# 5V.net
KiCad netlist of a schematic drawn in Altium Designer
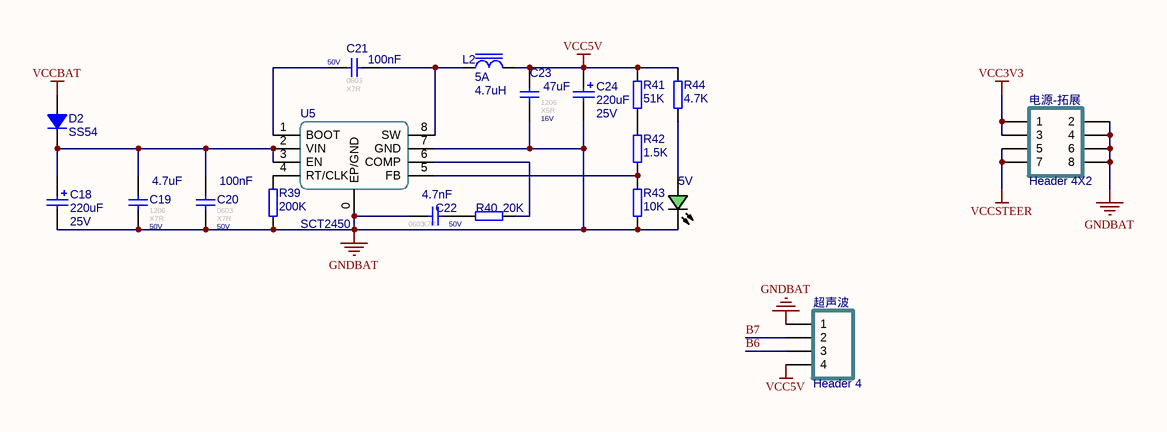
[diagram p0: 5V电源.SchDoc]

(export (version "E")
  (design (tool "Eeschema 10.0.6"))
  (components
    (comp (ref "5V")
      (value "翠绿贴片LED")
      (footprint "LEDC1608(0603)-L")
      (fields (field (name "PUBLISHER") "Altium Limited"))
      (libsource (lib "MM32F3277主板原理图库") (part "LED Chip Green"))
    )
    (comp (ref "C18")
      (value "220uF")
      (footprint "CAPS6.3")
      (description "Polarized Capacitor (Radial)")
      (fields
        (field (name "VOLTAGE") "25V")
        (field (name "Comment") "220uF 25V")
        (field (name "PUBLISHER") "Altium Limited")
      )
      (libsource (lib "MM32F3277主板原理图库") (part "Cap-Solid"))
    )
    (comp (ref "C19")
      (value "4.7uF")
      (footprint "1206")
      (description "贴片电容")
      (fields
        (field (name "TOLERANCE") "±10%")
        (field (name "TYPE") "X7R")
        (field (name "VOLTAGE") "50V")
        (field (name "Comment") "4.7uF ±10% 50V")
      )
      (libsource (lib "MM32F3277主板原理图库") (part "Cap-Chip_3"))
    )
    (comp (ref "C20")
      (value "100nF")
      (footprint "0603")
      (description "贴片电容")
      (fields
        (field (name "TOLERANCE") "±10%")
        (field (name "TYPE") "X7R")
        (field (name "VOLTAGE") "50V")
        (field (name "Comment") "100nF ±10% 50V")
      )
      (libsource (lib "MM32F3277主板原理图库") (part "Cap-Chip_2"))
    )
    (comp (ref "C21")
      (value "100nF")
      (footprint "0603")
      (description "贴片电容")
      (fields
        (field (name "TOLERANCE") "±10%")
        (field (name "TYPE") "X7R")
        (field (name "VOLTAGE") "50V")
        (field (name "Comment") "100nF ±10% 50V")
      )
      (libsource (lib "MM32F3277主板原理图库") (part "Cap-Chip_2"))
    )
    (comp (ref "C22")
      (value "4.7nF")
      (footprint "0603")
      (description "贴片电容")
      (fields
        (field (name "TOLERANCE") "±10%")
        (field (name "TYPE") "X7R")
        (field (name "VOLTAGE") "50V")
        (field (name "Comment") "4.7nF ±10% 50V")
      )
      (libsource (lib "MM32F3277主板原理图库") (part "Cap-Chip"))
    )
    (comp (ref "C23")
      (value "47uF")
      (footprint "1206")
      (description "贴片电容")
      (fields
        (field (name "TOLERANCE") "±10%")
        (field (name "TYPE") "X5R")
        (field (name "VOLTAGE") "16V")
        (field (name "Comment") "47uF ±10% 16V")
      )
      (libsource (lib "MM32F3277主板原理图库") (part "Cap-Chip_1"))
    )
    (comp (ref "C24")
      (value "220uF")
      (footprint "CAPS6.3")
      (description "Polarized Capacitor (Radial)")
      (fields
        (field (name "VOLTAGE") "25V")
        (field (name "Comment") "220uF 25V")
        (field (name "PUBLISHER") "Altium Limited")
      )
      (libsource (lib "MM32F3277主板原理图库") (part "Cap-Solid"))
    )
    (comp (ref "D2")
      (value "SS54")
      (footprint "SMA[DO-214AC]")
      (description "普通二极管 Diode")
      (fields (field (name "PUBLISHER") "Altium Limited"))
      (libsource (lib "MM32F3277主板原理图库") (part "Diode"))
    )
    (comp (ref "L2")
      (value "4.7uH")
      (footprint "0630 TPC 7*7*3")
      (description "功率电感")
      (fields
        (field (name "IMAX") "5A")
        (field (name "Comment") "4.7uH 5A")
        (field (name "PUBLISHER") "Altium Limited")
      )
      (libsource (lib "MM32F3277主板原理图库") (part "Ind-Power"))
    )
    (comp (ref "R39")
      (value "200K")
      (footprint "RESC1608[0603]S-N")
      (description "贴片电阻")
      (fields (field (name "TOLERANCE") "±1%") (field (name "Comment") "200K ±1%"))
      (libsource (lib "MM32F3277主板原理图库") (part "Res-Chip"))
    )
    (comp (ref "R40")
      (value "20K")
      (footprint "RESC1608[0603]S-N")
      (description "贴片电阻")
      (fields (field (name "TOLERANCE") "±1%") (field (name "Comment") "20K ±1%"))
      (libsource (lib "MM32F3277主板原理图库") (part "Res-Chip_1"))
    )
    (comp (ref "R41")
      (value "51K")
      (footprint "RESC1608[0603]S-N")
      (description "贴片电阻")
      (fields (field (name "TOLERANCE") "±1%") (field (name "Comment") "51K ±1%"))
      (libsource (lib "MM32F3277主板原理图库") (part "Res-Chip_2"))
    )
    (comp (ref "R42")
      (value "1.5K")
      (footprint "RESC1608[0603]S-N")
      (description "贴片电阻")
      (fields (field (name "TOLERANCE") "±1%") (field (name "Comment") "1.5K ±1%"))
      (libsource (lib "MM32F3277主板原理图库") (part "Res-Chip_4"))
    )
    (comp (ref "R43")
      (value "10K")
      (footprint "RESC1608[0603]S-N")
      (description "贴片电阻")
      (fields (field (name "TOLERANCE") "±1%") (field (name "Comment") "10K ±1%"))
      (libsource (lib "MM32F3277主板原理图库") (part "Res-Chip_3"))
    )
    (comp (ref "R44")
      (value "4.7K")
      (footprint "RESC1608[0603]S-N")
      (description "贴片电阻")
      (fields (field (name "TOLERANCE") "±1%") (field (name "Comment") "4.7K ±1%"))
      (libsource (lib "MM32F3277主板原理图库") (part "Res-Chip_5"))
    )
    (comp (ref "U5")
      (value "SCT2450")
      (footprint "SOP-8E")
      (libsource (lib "MM32F3277主板原理图库") (part "SCT2450"))
    )
    (comp (ref "电源-拓展")
      (value "Header 4X2")
      (footprint "HDR2X4-F-SMT")
      (description "Header, 4-Pin, Dual row")
      (fields (field (name "PUBLISHER") "Altium Limited"))
      (libsource (lib "MM32F3277主板原理图库") (part "Header 4X2"))
    )
    (comp (ref "超声波")
      (value "Header 4")
      (footprint "HDR1X4")
      (description "Header, 4-Pin")
      (fields (field (name "PUBLISHER") "Altium Limited"))
      (libsource (lib "MM32F3277主板原理图库") (part "Header 4"))
    )
  )
  (nets
    (net (code "1") (name "/B6") (class "Default")
      (node (ref "超声波") (pin "3") (pinfunction "3_3") (pintype "passive"))
    )
    (net (code "2") (name "/B7") (class "Default")
      (node (ref "超声波") (pin "2") (pinfunction "2_2") (pintype "passive"))
    )
    (net (code "3") (name "GNDBAT") (class "Default")
      (node (ref "5V") (pin "C") (pinfunction "C_C") (pintype "passive"))
      (node (ref "C18") (pin "2") (pinfunction "2_2") (pintype "passive"))
      (node (ref "C19") (pin "1") (pinfunction "1_1") (pintype "passive"))
      (node (ref "C20") (pin "1") (pinfunction "1_1") (pintype "passive"))
      (node (ref "C22") (pin "1") (pinfunction "1_1") (pintype "passive"))
      (node (ref "C23") (pin "1") (pinfunction "1_1") (pintype "passive"))
      (node (ref "C24") (pin "2") (pinfunction "2_2") (pintype "passive"))
      (node (ref "R39") (pin "1") (pinfunction "1_1") (pintype "passive"))
      (node (ref "R43") (pin "2") (pinfunction "2_2") (pintype "passive"))
      (node (ref "U5") (pin "0") (pinfunction "EP/GND_0") (pintype "passive"))
      (node (ref "U5") (pin "7") (pinfunction "GND_7") (pintype "passive"))
      (node (ref "电源-拓展") (pin "2") (pinfunction "2_2") (pintype "passive"))
      (node (ref "电源-拓展") (pin "4") (pinfunction "4_4") (pintype "passive"))
      (node (ref "电源-拓展") (pin "6") (pinfunction "6_6") (pintype "passive"))
      (node (ref "电源-拓展") (pin "8") (pinfunction "8_8") (pintype "passive"))
      (node (ref "超声波") (pin "1") (pinfunction "1_1") (pintype "passive"))
    )
    (net (code "4") (name "Net-(5V-PadA)") (class "Default")
      (node (ref "5V") (pin "A") (pinfunction "A_A") (pintype "passive"))
      (node (ref "R44") (pin "2") (pinfunction "2_2") (pintype "passive"))
    )
    (net (code "5") (name "Net-(C22-Pad2)") (class "Default")
      (node (ref "C22") (pin "2") (pinfunction "2_2") (pintype "passive"))
      (node (ref "R40") (pin "1") (pinfunction "1_1") (pintype "passive"))
    )
    (net (code "6") (name "Net-(R41-Pad2)") (class "Default")
      (node (ref "R41") (pin "2") (pinfunction "2_2") (pintype "passive"))
      (node (ref "R42") (pin "1") (pinfunction "1_1") (pintype "passive"))
    )
    (net (code "7") (name "Net-(U5-BOOT)") (class "Default")
      (node (ref "C21") (pin "1") (pinfunction "1_1") (pintype "passive"))
      (node (ref "U5") (pin "1") (pinfunction "BOOT_1") (pintype "passive"))
    )
    (net (code "8") (name "Net-(U5-COMP)") (class "Default")
      (node (ref "R40") (pin "2") (pinfunction "2_2") (pintype "passive"))
      (node (ref "U5") (pin "6") (pinfunction "COMP_6") (pintype "passive"))
    )
    (net (code "9") (name "Net-(U5-EN)") (class "Default")
      (node (ref "C18") (pin "1") (pinfunction "1_1") (pintype "passive"))
      (node (ref "C19") (pin "2") (pinfunction "2_2") (pintype "passive"))
      (node (ref "C20") (pin "2") (pinfunction "2_2") (pintype "passive"))
      (node (ref "D2") (pin "K") (pinfunction "K_K") (pintype "passive"))
      (node (ref "U5") (pin "2") (pinfunction "VIN_2") (pintype "passive"))
      (node (ref "U5") (pin "3") (pinfunction "EN_3") (pintype "passive"))
    )
    (net (code "10") (name "Net-(U5-FB)") (class "Default")
      (node (ref "R42") (pin "2") (pinfunction "2_2") (pintype "passive"))
      (node (ref "R43") (pin "1") (pinfunction "1_1") (pintype "passive"))
      (node (ref "U5") (pin "5") (pinfunction "FB_5") (pintype "passive"))
    )
    (net (code "11") (name "Net-(U5-RT{slash}CLK)") (class "Default")
      (node (ref "R39") (pin "2") (pinfunction "2_2") (pintype "passive"))
      (node (ref "U5") (pin "4") (pinfunction "RT/CLK_4") (pintype "passive"))
    )
    (net (code "12") (name "Net-(U5-SW)") (class "Default")
      (node (ref "C21") (pin "2") (pinfunction "2_2") (pintype "passive"))
      (node (ref "L2") (pin "1") (pinfunction "1_1") (pintype "passive"))
      (node (ref "U5") (pin "8") (pinfunction "SW_8") (pintype "passive"))
    )
    (net (code "13") (name "VCC3V3") (class "Default")
      (node (ref "电源-拓展") (pin "1") (pinfunction "1_1") (pintype "passive"))
      (node (ref "电源-拓展") (pin "3") (pinfunction "3_3") (pintype "passive"))
    )
    (net (code "14") (name "VCC5V") (class "Default")
      (node (ref "C23") (pin "2") (pinfunction "2_2") (pintype "passive"))
      (node (ref "C24") (pin "1") (pinfunction "1_1") (pintype "passive"))
      (node (ref "L2") (pin "2") (pinfunction "2_2") (pintype "passive"))
      (node (ref "R41") (pin "1") (pinfunction "1_1") (pintype "passive"))
      (node (ref "R44") (pin "1") (pinfunction "1_1") (pintype "passive"))
      (node (ref "超声波") (pin "4") (pinfunction "4_4") (pintype "passive"))
    )
    (net (code "15") (name "VCCBAT") (class "Default")
      (node (ref "D2") (pin "A") (pinfunction "A_A") (pintype "passive"))
    )
    (net (code "16") (name "VCCSTEER") (class "Default")
      (node (ref "电源-拓展") (pin "5") (pinfunction "5_5") (pintype "passive"))
      (node (ref "电源-拓展") (pin "7") (pinfunction "7_7") (pintype "passive"))
    )
  )
)
